# V2c.net
KiCad netlist of a schematic drawn in EAGLE
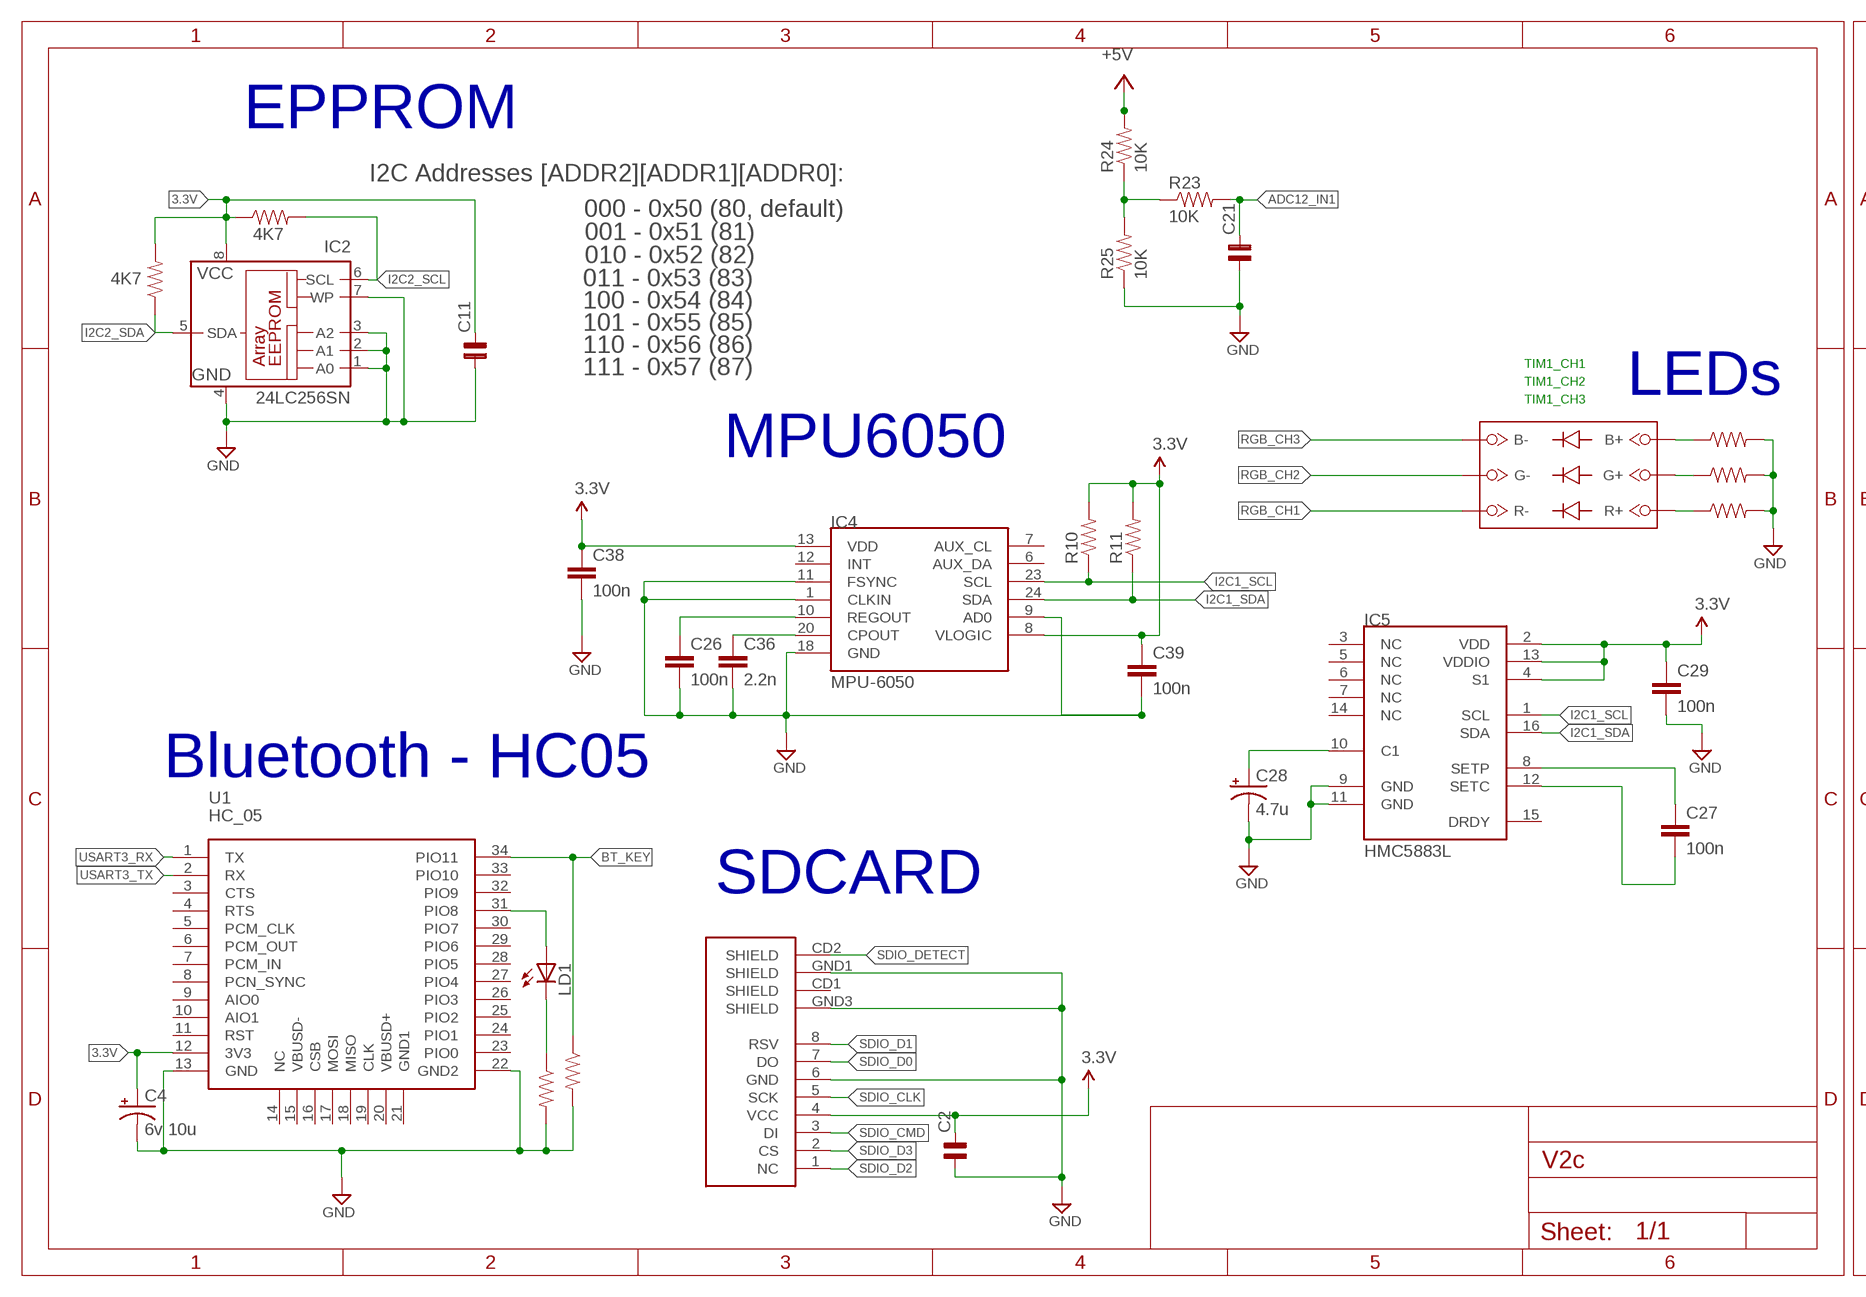
[diagram p0: schematic, sheet 1, part 1 of 2]
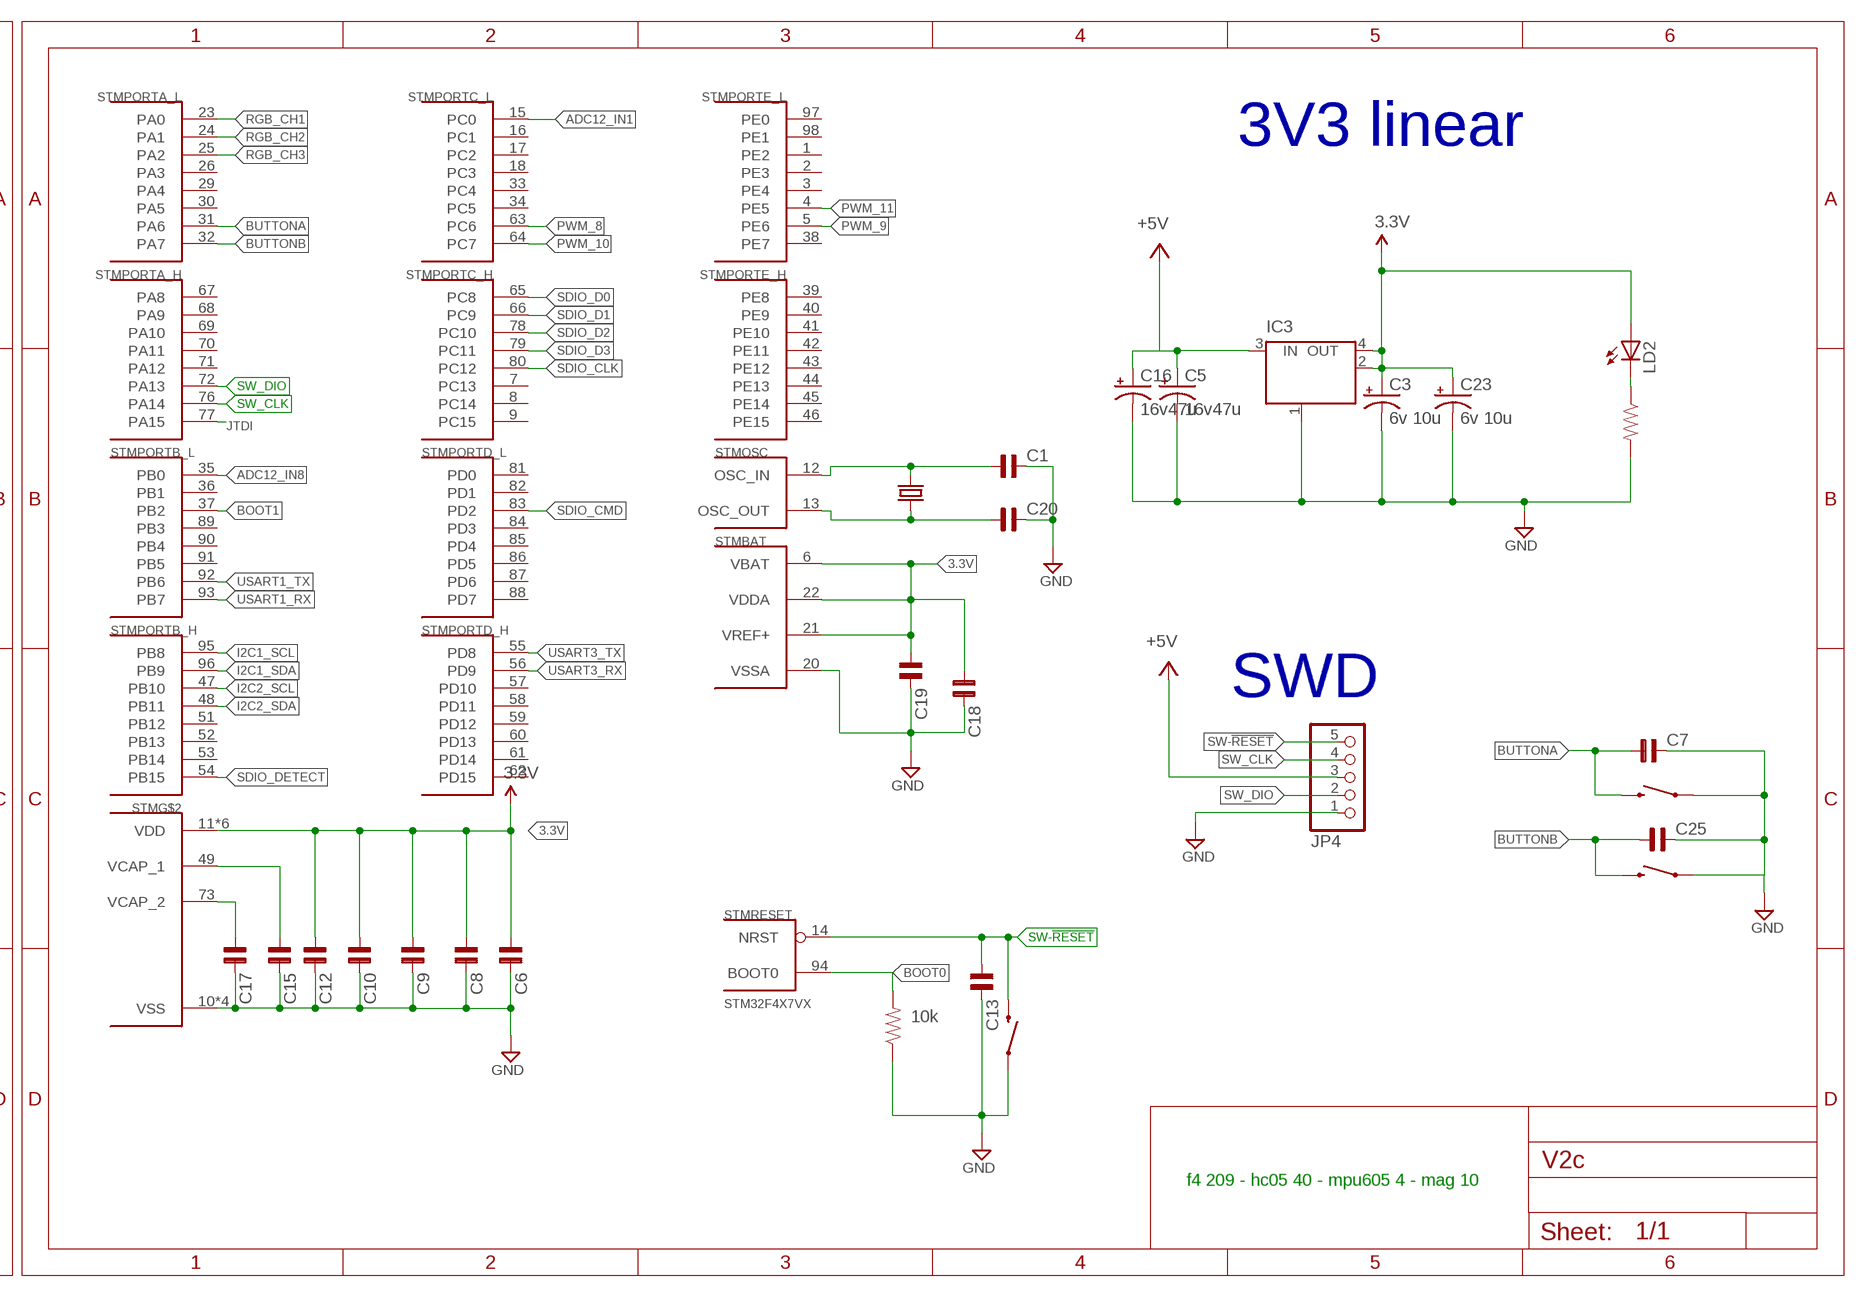
[diagram p1: schematic, sheet 1, part 2 of 2]

(export (version "E")
  (design (tool "Eeschema 10.0.6"))
  (components
    (comp (ref "C1")
      (value "C-NP-SMD-0603")
      (footprint "eagle-import:C-0603")
      (libsource (lib "eagle-import") (part "C-NP-SMD-0603"))
    )
    (comp (ref "C2")
      (value "C-NP-SMD-0603")
      (footprint "eagle-import:C-0603")
      (libsource (lib "eagle-import") (part "C-NP-SMD-0603"))
    )
    (comp (ref "C3")
      (value "6v 10u")
      (footprint "eagle-import:SMC_C")
      (libsource (lib "eagle-import") (part "CPOL-USSMCC"))
    )
    (comp (ref "C4")
      (value "6v 10u")
      (footprint "eagle-import:SMC_A")
      (libsource (lib "eagle-import") (part "CPOL-USSMCA"))
    )
    (comp (ref "C5")
      (value "16v47u")
      (footprint "eagle-import:SMC_C")
      (libsource (lib "eagle-import") (part "CPOL-USSMCC"))
    )
    (comp (ref "C6")
      (value "C-NP-SMD-0603")
      (footprint "eagle-import:C-0603")
      (libsource (lib "eagle-import") (part "C-NP-SMD-0603"))
    )
    (comp (ref "C7")
      (value "C-NP-SMD-0603")
      (footprint "eagle-import:C-0603")
      (libsource (lib "eagle-import") (part "C-NP-SMD-0603"))
    )
    (comp (ref "C8")
      (value "C-NP-SMD-0603")
      (footprint "eagle-import:C-0603")
      (libsource (lib "eagle-import") (part "C-NP-SMD-0603"))
    )
    (comp (ref "C9")
      (value "C-NP-SMD-0603")
      (footprint "eagle-import:C-0603")
      (libsource (lib "eagle-import") (part "C-NP-SMD-0603"))
    )
    (comp (ref "C10")
      (value "C-NP-SMD-0603")
      (footprint "eagle-import:C-0603")
      (libsource (lib "eagle-import") (part "C-NP-SMD-0603"))
    )
    (comp (ref "C11")
      (value "C-NP-SMD-0603")
      (footprint "eagle-import:C-0603")
      (libsource (lib "eagle-import") (part "C-NP-SMD-0603"))
    )
    (comp (ref "C12")
      (value "C-NP-SMD-0603")
      (footprint "eagle-import:C-0603")
      (libsource (lib "eagle-import") (part "C-NP-SMD-0603"))
    )
    (comp (ref "C13")
      (value "C-NP-SMD-0603")
      (footprint "eagle-import:C-0603")
      (libsource (lib "eagle-import") (part "C-NP-SMD-0603"))
    )
    (comp (ref "C15")
      (value "C-NP-SMD-0603")
      (footprint "eagle-import:C-0603")
      (libsource (lib "eagle-import") (part "C-NP-SMD-0603"))
    )
    (comp (ref "C16")
      (value "16v47u")
      (footprint "eagle-import:SMC_C")
      (libsource (lib "eagle-import") (part "CPOL-USSMCC"))
    )
    (comp (ref "C17")
      (value "C-NP-SMD-0603")
      (footprint "eagle-import:C-0603")
      (libsource (lib "eagle-import") (part "C-NP-SMD-0603"))
    )
    (comp (ref "C18")
      (value "C-NP-SMD-0603")
      (footprint "eagle-import:C-0603")
      (libsource (lib "eagle-import") (part "C-NP-SMD-0603"))
    )
    (comp (ref "C19")
      (value "C-NP-SMD-0603")
      (footprint "eagle-import:C-0603")
      (libsource (lib "eagle-import") (part "C-NP-SMD-0603"))
    )
    (comp (ref "C20")
      (value "C-NP-SMD-0603")
      (footprint "eagle-import:C-0603")
      (libsource (lib "eagle-import") (part "C-NP-SMD-0603"))
    )
    (comp (ref "C21")
      (value "C-NP-SMD-0603")
      (footprint "eagle-import:C-0603")
      (libsource (lib "eagle-import") (part "C-NP-SMD-0603"))
    )
    (comp (ref "C23")
      (value "6v 10u")
      (footprint "eagle-import:SMC_C")
      (libsource (lib "eagle-import") (part "CPOL-USSMCC"))
    )
    (comp (ref "C25")
      (value "C-NP-SMD-0603")
      (footprint "eagle-import:C-0603")
      (libsource (lib "eagle-import") (part "C-NP-SMD-0603"))
    )
    (comp (ref "C26")
      (value "100n")
      (footprint "eagle-import:SPARKFUN_0603-CAP")
      (libsource (lib "eagle-import") (part "SPARKFUN_CAP0603-CAP"))
    )
    (comp (ref "C27")
      (value "100n")
      (footprint "eagle-import:SPARKFUN_0603-CAP")
      (libsource (lib "eagle-import") (part "SPARKFUN_CAP0603-CAP"))
    )
    (comp (ref "C28")
      (value "4.7u")
      (footprint "eagle-import:SMC_A")
      (libsource (lib "eagle-import") (part "CPOL-USSMCA"))
    )
    (comp (ref "C29")
      (value "100n")
      (footprint "eagle-import:SPARKFUN_0603-CAP")
      (libsource (lib "eagle-import") (part "SPARKFUN_CAP0603-CAP"))
    )
    (comp (ref "C36")
      (value "2.2n")
      (footprint "eagle-import:SPARKFUN_0603-CAP")
      (libsource (lib "eagle-import") (part "SPARKFUN_CAP0603-CAP"))
    )
    (comp (ref "C38")
      (value "100n")
      (footprint "eagle-import:SPARKFUN_0603-CAP")
      (libsource (lib "eagle-import") (part "SPARKFUN_CAP0603-CAP"))
    )
    (comp (ref "C39")
      (value "100n")
      (footprint "eagle-import:SPARKFUN_0603-CAP")
      (libsource (lib "eagle-import") (part "SPARKFUN_CAP0603-CAP"))
    )
    (comp (ref "IC2")
      (value "24LC256SN")
      (footprint "eagle-import:SO-08")
      (fields (field (name "MF") "MICROCHIP") (field (name "MPN") "24LC256-I/SN"))
      (libsource (lib "eagle-import") (part "24SNLC256"))
    )
    (comp (ref "IC3")
      (value "LINEAR_MC33269ST-3.3T3")
      (footprint "eagle-import:LINEAR_SOT223")
      (libsource (lib "eagle-import") (part "LINEAR_MC33269ST-3.3T3"))
    )
    (comp (ref "IC4")
      (value "MPU-6050")
      (footprint "eagle-import:TESTING_QFN-24-4MM2")
      (libsource (lib "eagle-import") (part "TESTING_MPU-6050-1"))
    )
    (comp (ref "IC5")
      (value "HMC5883L")
      (footprint "eagle-import:SPARKFUN_16LPCC")
      (libsource (lib "eagle-import") (part "SPARKFUN_HMC5883LSMD"))
    )
    (comp (ref "JP4")
      (value "PINHD-1X5_2.54-90°")
      (footprint "eagle-import:1X05_90")
      (libsource (lib "eagle-import") (part "PINHD-1X5_2.54-90°"))
    )
    (comp (ref "LD1")
      (value "LEDCHIPLED_0603")
      (footprint "eagle-import:CHIPLED_0603")
      (libsource (lib "eagle-import") (part "LEDCHIPLED_0603"))
    )
    (comp (ref "LD2")
      (value "LEDCHIPLED_0603")
      (footprint "eagle-import:CHIPLED_0603")
      (libsource (lib "eagle-import") (part "LEDCHIPLED_0603"))
    )
    (comp (ref "R1")
      (value "10K")
      (footprint "eagle-import:SPARKFUN_0603-RES")
      (libsource (lib "eagle-import") (part "Robotech_RCL_SPARKFUN_RESISTOR0603-RES"))
    )
    (comp (ref "R2")
      (value "10K")
      (footprint "eagle-import:SPARKFUN_0603-RES")
      (libsource (lib "eagle-import") (part "Robotech_RCL_SPARKFUN_RESISTOR0603-RES"))
    )
    (comp (ref "R3")
      (value "10K")
      (footprint "eagle-import:SPARKFUN_0603-RES")
      (libsource (lib "eagle-import") (part "Robotech_RCL_SPARKFUN_RESISTOR0603-RES"))
    )
    (comp (ref "R5")
      (value "10K")
      (footprint "eagle-import:SPARKFUN_0603-RES")
      (libsource (lib "eagle-import") (part "Robotech_RCL_SPARKFUN_RESISTOR0603-RES"))
    )
    (comp (ref "R6")
      (value "10K")
      (footprint "eagle-import:SPARKFUN_0603-RES")
      (libsource (lib "eagle-import") (part "Robotech_RCL_SPARKFUN_RESISTOR0603-RES"))
    )
    (comp (ref "R7")
      (value "10k")
      (footprint "eagle-import:SPARKFUN_0603-RES")
      (libsource (lib "eagle-import") (part "Robotech_RCL_SPARKFUN_RESISTOR0603-RES"))
    )
    (comp (ref "R9")
      (value "10K")
      (footprint "eagle-import:SPARKFUN_0603-RES")
      (libsource (lib "eagle-import") (part "Robotech_RCL_SPARKFUN_RESISTOR0603-RES"))
    )
    (comp (ref "R10")
      (value "SPARKFUN_RESISTOR0603-RES")
      (footprint "eagle-import:SPARKFUN_0603-RES")
      (libsource (lib "eagle-import") (part "SPARKFUN_RESISTOR0603-RES"))
    )
    (comp (ref "R11")
      (value "SPARKFUN_RESISTOR0603-RES")
      (footprint "eagle-import:SPARKFUN_0603-RES")
      (libsource (lib "eagle-import") (part "SPARKFUN_RESISTOR0603-RES"))
    )
    (comp (ref "R15")
      (value "4K7")
      (footprint "eagle-import:SPARKFUN_0603-RES")
      (libsource (lib "eagle-import") (part "Robotech_RCL_SPARKFUN_RESISTOR0603-RES"))
    )
    (comp (ref "R16")
      (value "4K7")
      (footprint "eagle-import:SPARKFUN_0603-RES")
      (libsource (lib "eagle-import") (part "Robotech_RCL_SPARKFUN_RESISTOR0603-RES"))
    )
    (comp (ref "R23")
      (value "10K")
      (footprint "eagle-import:SPARKFUN_0603-RES")
      (libsource (lib "eagle-import") (part "Robotech_RCL_SPARKFUN_RESISTOR0603-RES"))
    )
    (comp (ref "R24")
      (value "10K")
      (footprint "eagle-import:SPARKFUN_0603-RES")
      (libsource (lib "eagle-import") (part "Robotech_RCL_SPARKFUN_RESISTOR0603-RES"))
    )
    (comp (ref "R25")
      (value "10K")
      (footprint "eagle-import:SPARKFUN_0603-RES")
      (libsource (lib "eagle-import") (part "Robotech_RCL_SPARKFUN_RESISTOR0603-RES"))
    )
    (comp (ref "S1")
      (value "RESET")
      (footprint "eagle-import:TACTILE-SWITCH-1101NE")
      (fields (field (name "PARTNO") "EVQ-P7J01P"))
      (libsource (lib "eagle-import") (part "SWITCH-MOMENTARY-2-SMD-1101NE"))
    )
    (comp (ref "S2")
      (value "RESET")
      (footprint "eagle-import:TACTILE-SWITCH-1101NE")
      (fields (field (name "PARTNO") "EVQ-P7J01P"))
      (libsource (lib "eagle-import") (part "SWITCH-MOMENTARY-2-SMD-1101NE"))
    )
    (comp (ref "S4")
      (value "RESET")
      (footprint "eagle-import:TACTILE-SWITCH-1101NE")
      (fields (field (name "PARTNO") "EVQ-P7J01P"))
      (libsource (lib "eagle-import") (part "SWITCH-MOMENTARY-2-SMD-1101NE"))
    )
    (comp (ref "SDCARD2")
      (value "microSD Socket")
      (footprint "eagle-import:MICRO-SD-SOCKET-PP")
      (libsource (lib "eagle-import") (part "USD-SOCKETNEW"))
    )
    (comp (ref "STM")
      (value "STM32F4X7VX")
      (footprint "eagle-import:TQFP100")
      (fields (field (name "PARTNO") "STM32F427VI"))
      (libsource (lib "eagle-import") (part "STM32F4X7VX"))
    )
    (comp (ref "U$12")
      (value "RGB_LED")
      (footprint "eagle-import:SMD")
      (libsource (lib "eagle-import") (part "RGB_LED"))
    )
    (comp (ref "U1")
      (value "HC_05")
      (footprint "eagle-import:BLUETOOTH_SMD")
      (libsource (lib "eagle-import") (part "HC_05"))
    )
    (comp (ref "Y1")
      (value "CRYSTALHC49US")
      (footprint "eagle-import:HC49US")
      (libsource (lib "eagle-import") (part "CRYSTALHC49US"))
    )
  )
  (nets
    (net (code "1") (name "+5V") (class "Default")
      (node (ref "C16") (pin "+") (pinfunction "+_+") (pintype "passive"))
      (node (ref "C5") (pin "+") (pinfunction "+_+") (pintype "passive"))
      (node (ref "IC3") (pin "3") (pinfunction "IN_3") (pintype "input"))
      (node (ref "JP4") (pin "3") (pinfunction "3_3") (pintype "passive"))
      (node (ref "R24") (pin "2") (pinfunction "2_2") (pintype "passive"))
    )
    (net (code "2") (name "/JTDI") (class "Default")
      (node (ref "STM") (pin "77") (pinfunction "PA15_77") (pintype "bidirectional"))
    )
    (net (code "3") (name "/SW-~{RESET}") (class "Default")
      (node (ref "C13") (pin "1") (pinfunction "1_1") (pintype "passive"))
      (node (ref "JP4") (pin "5") (pinfunction "5_5") (pintype "passive"))
      (node (ref "S1") (pin "P$2") (pinfunction "2_P$2") (pintype "passive"))
      (node (ref "STM") (pin "14") (pinfunction "NRST_14") (pintype "input"))
    )
    (net (code "4") (name "3.3V") (class "Default")
      (node (ref "C10") (pin "1") (pinfunction "1_1") (pintype "passive"))
      (node (ref "C11") (pin "2") (pinfunction "2_2") (pintype "passive"))
      (node (ref "C12") (pin "1") (pinfunction "1_1") (pintype "passive"))
      (node (ref "C18") (pin "1") (pinfunction "1_1") (pintype "passive"))
      (node (ref "C19") (pin "1") (pinfunction "1_1") (pintype "passive"))
      (node (ref "C2") (pin "2") (pinfunction "2_2") (pintype "passive"))
      (node (ref "C23") (pin "+") (pinfunction "+_+") (pintype "passive"))
      (node (ref "C29") (pin "1") (pinfunction "1_1") (pintype "passive"))
      (node (ref "C3") (pin "+") (pinfunction "+_+") (pintype "passive"))
      (node (ref "C38") (pin "1") (pinfunction "1_1") (pintype "passive"))
      (node (ref "C39") (pin "1") (pinfunction "1_1") (pintype "passive"))
      (node (ref "C4") (pin "+") (pinfunction "+_+") (pintype "passive"))
      (node (ref "C6") (pin "1") (pinfunction "1_1") (pintype "passive"))
      (node (ref "C8") (pin "1") (pinfunction "1_1") (pintype "passive"))
      (node (ref "C9") (pin "1") (pinfunction "1_1") (pintype "passive"))
      (node (ref "IC2") (pin "8") (pinfunction "VCC_8") (pintype "power_in"))
      (node (ref "IC3") (pin "2") (pinfunction "OUT_2") (pintype "passive"))
      (node (ref "IC3") (pin "4") (pinfunction "OUT_4") (pintype "passive"))
      (node (ref "IC4") (pin "13") (pinfunction "VDD_13") (pintype "bidirectional"))
      (node (ref "IC4") (pin "8") (pinfunction "VLOGIC_8") (pintype "bidirectional"))
      (node (ref "IC5") (pin "13") (pinfunction "VDDIO_13") (pintype "bidirectional"))
      (node (ref "IC5") (pin "2") (pinfunction "VDD_2") (pintype "bidirectional"))
      (node (ref "IC5") (pin "4") (pinfunction "S1_4") (pintype "bidirectional"))
      (node (ref "LD2") (pin "A") (pinfunction "A_A") (pintype "passive"))
      (node (ref "R10") (pin "2") (pinfunction "2_2") (pintype "passive"))
      (node (ref "R11") (pin "2") (pinfunction "2_2") (pintype "passive"))
      (node (ref "R15") (pin "1") (pinfunction "1_1") (pintype "passive"))
      (node (ref "R16") (pin "2") (pinfunction "2_2") (pintype "passive"))
      (node (ref "SDCARD2") (pin "4") (pinfunction "VCC_4") (pintype "bidirectional"))
      (node (ref "STM") (pin "100") (pinfunction "VDD_100") (pintype "power_in"))
      (node (ref "STM") (pin "11") (pinfunction "VDD_11") (pintype "power_in"))
      (node (ref "STM") (pin "19") (pinfunction "VDD_19") (pintype "power_in"))
      (node (ref "STM") (pin "21") (pinfunction "VREF+_21") (pintype "input"))
      (node (ref "STM") (pin "22") (pinfunction "VDDA_22") (pintype "power_in"))
      (node (ref "STM") (pin "28") (pinfunction "VDD_28") (pintype "power_in"))
      (node (ref "STM") (pin "50") (pinfunction "VDD_50") (pintype "power_in"))
      (node (ref "STM") (pin "6") (pinfunction "VBAT_6") (pintype "power_in"))
      (node (ref "STM") (pin "75") (pinfunction "VDD_75") (pintype "power_in"))
      (node (ref "U1") (pin "12") (pinfunction "3V3_12") (pintype "bidirectional"))
    )
    (net (code "5") (name "ADC12_IN1") (class "Default")
      (node (ref "C21") (pin "2") (pinfunction "2_2") (pintype "passive"))
      (node (ref "R23") (pin "2") (pinfunction "2_2") (pintype "passive"))
      (node (ref "STM") (pin "15") (pinfunction "PC0_15") (pintype "bidirectional"))
    )
    (net (code "6") (name "ADC12_IN8") (class "Default")
      (node (ref "STM") (pin "35") (pinfunction "PB0_35") (pintype "bidirectional"))
    )
    (net (code "7") (name "BOOT0") (class "Default")
      (node (ref "R7") (pin "2") (pinfunction "2_2") (pintype "passive"))
      (node (ref "STM") (pin "94") (pinfunction "BOOT0_94") (pintype "input"))
    )
    (net (code "8") (name "BOOT1") (class "Default")
      (node (ref "STM") (pin "37") (pinfunction "PB2_37") (pintype "bidirectional"))
    )
    (net (code "9") (name "BT_KEY") (class "Default")
      (node (ref "R5") (pin "1") (pinfunction "1_1") (pintype "passive"))
      (node (ref "U1") (pin "34") (pinfunction "PIO11_34") (pintype "bidirectional"))
    )
    (net (code "10") (name "BUTTONA") (class "Default")
      (node (ref "C7") (pin "1") (pinfunction "1_1") (pintype "passive"))
      (node (ref "S4") (pin "P$2") (pinfunction "2_P$2") (pintype "passive"))
      (node (ref "STM") (pin "31") (pinfunction "PA6_31") (pintype "bidirectional"))
    )
    (net (code "11") (name "BUTTONB") (class "Default")
      (node (ref "C25") (pin "1") (pinfunction "1_1") (pintype "passive"))
      (node (ref "S2") (pin "P$2") (pinfunction "2_P$2") (pintype "passive"))
      (node (ref "STM") (pin "32") (pinfunction "PA7_32") (pintype "bidirectional"))
    )
    (net (code "12") (name "GND") (class "Default")
      (node (ref "C1") (pin "2") (pinfunction "2_2") (pintype "passive"))
      (node (ref "C10") (pin "2") (pinfunction "2_2") (pintype "passive"))
      (node (ref "C11") (pin "1") (pinfunction "1_1") (pintype "passive"))
      (node (ref "C12") (pin "2") (pinfunction "2_2") (pintype "passive"))
      (node (ref "C13") (pin "2") (pinfunction "2_2") (pintype "passive"))
      (node (ref "C15") (pin "2") (pinfunction "2_2") (pintype "passive"))
      (node (ref "C16") (pin "-") (pinfunction "-_-") (pintype "passive"))
      (node (ref "C17") (pin "2") (pinfunction "2_2") (pintype "passive"))
      (node (ref "C18") (pin "2") (pinfunction "2_2") (pintype "passive"))
      (node (ref "C19") (pin "2") (pinfunction "2_2") (pintype "passive"))
      (node (ref "C2") (pin "1") (pinfunction "1_1") (pintype "passive"))
      (node (ref "C20") (pin "2") (pinfunction "2_2") (pintype "passive"))
      (node (ref "C21") (pin "1") (pinfunction "1_1") (pintype "passive"))
      (node (ref "C23") (pin "-") (pinfunction "-_-") (pintype "passive"))
      (node (ref "C25") (pin "2") (pinfunction "2_2") (pintype "passive"))
      (node (ref "C26") (pin "2") (pinfunction "2_2") (pintype "passive"))
      (node (ref "C28") (pin "-") (pinfunction "-_-") (pintype "passive"))
      (node (ref "C29") (pin "2") (pinfunction "2_2") (pintype "passive"))
      (node (ref "C3") (pin "-") (pinfunction "-_-") (pintype "passive"))
      (node (ref "C36") (pin "2") (pinfunction "2_2") (pintype "passive"))
      (node (ref "C38") (pin "2") (pinfunction "2_2") (pintype "passive"))
      (node (ref "C39") (pin "2") (pinfunction "2_2") (pintype "passive"))
      (node (ref "C4") (pin "-") (pinfunction "-_-") (pintype "passive"))
      (node (ref "C5") (pin "-") (pinfunction "-_-") (pintype "passive"))
      (node (ref "C6") (pin "2") (pinfunction "2_2") (pintype "passive"))
      (node (ref "C7") (pin "2") (pinfunction "2_2") (pintype "passive"))
      (node (ref "C8") (pin "2") (pinfunction "2_2") (pintype "passive"))
      (node (ref "C9") (pin "2") (pinfunction "2_2") (pintype "passive"))
      (node (ref "IC2") (pin "1") (pinfunction "A0_1") (pintype "input"))
      (node (ref "IC2") (pin "2") (pinfunction "A1_2") (pintype "input"))
      (node (ref "IC2") (pin "3") (pinfunction "A2_3") (pintype "input"))
      (node (ref "IC2") (pin "4") (pinfunction "GND_4") (pintype "power_in"))
      (node (ref "IC2") (pin "7") (pinfunction "WP_7") (pintype "input"))
      (node (ref "IC3") (pin "1") (pinfunction "GND/ADJ_1") (pintype "input"))
      (node (ref "IC4") (pin "1") (pinfunction "CLKIN_1") (pintype "bidirectional"))
      (node (ref "IC4") (pin "11") (pinfunction "FSYNC_11") (pintype "bidirectional"))
      (node (ref "IC4") (pin "18") (pinfunction "GND_18") (pintype "bidirectional"))
      (node (ref "IC4") (pin "9") (pinfunction "AD0_9") (pintype "bidirectional"))
      (node (ref "IC5") (pin "11") (pinfunction "GND_11") (pintype "bidirectional"))
      (node (ref "IC5") (pin "9") (pinfunction "GND_9") (pintype "bidirectional"))
      (node (ref "JP4") (pin "1") (pinfunction "1_1") (pintype "passive"))
      (node (ref "R1") (pin "2") (pinfunction "2_2") (pintype "passive"))
      (node (ref "R2") (pin "2") (pinfunction "2_2") (pintype "passive"))
      (node (ref "R25") (pin "1") (pinfunction "1_1") (pintype "passive"))
      (node (ref "R3") (pin "2") (pinfunction "2_2") (pintype "passive"))
      (node (ref "R5") (pin "2") (pinfunction "2_2") (pintype "passive"))
      (node (ref "R6") (pin "2") (pinfunction "2_2") (pintype "passive"))
      (node (ref "R7") (pin "1") (pinfunction "1_1") (pintype "passive"))
      (node (ref "R9") (pin "2") (pinfunction "2_2") (pintype "passive"))
      (node (ref "S1") (pin "P$1") (pinfunction "1_P$1") (pintype "passive"))
      (node (ref "S2") (pin "P$1") (pinfunction "1_P$1") (pintype "passive"))
      (node (ref "S4") (pin "P$1") (pinfunction "1_P$1") (pintype "passive"))
      (node (ref "SDCARD2") (pin "6") (pinfunction "GND_6") (pintype "bidirectional"))
      (node (ref "SDCARD2") (pin "GND1") (pinfunction "SHIELD_GND1") (pintype "bidirectional"))
      (node (ref "SDCARD2") (pin "GND3") (pinfunction "SHIELD_GND3") (pintype "bidirectional"))
      (node (ref "STM") (pin "10") (pinfunction "VSS_10") (pintype "power_in"))
      (node (ref "STM") (pin "20") (pinfunction "VSSA_20") (pintype "power_in"))
      (node (ref "STM") (pin "27") (pinfunction "VSS_27") (pintype "power_in"))
      (node (ref "STM") (pin "74") (pinfunction "VSS_74") (pintype "power_in"))
      (node (ref "STM") (pin "99") (pinfunction "VSS_99") (pintype "power_in"))
      (node (ref "U1") (pin "13") (pinfunction "GND_13") (pintype "bidirectional"))
      (node (ref "U1") (pin "22") (pinfunction "GND2_22") (pintype "bidirectional"))
    )
    (net (code "13") (name "I2C1_SCL") (class "Default")
      (node (ref "IC4") (pin "23") (pinfunction "SCL_23") (pintype "bidirectional"))
      (node (ref "IC5") (pin "1") (pinfunction "SCL_1") (pintype "bidirectional"))
      (node (ref "R10") (pin "1") (pinfunction "1_1") (pintype "passive"))
      (node (ref "STM") (pin "95") (pinfunction "PB8_95") (pintype "bidirectional"))
    )
    (net (code "14") (name "I2C1_SDA") (class "Default")
      (node (ref "IC4") (pin "24") (pinfunction "SDA_24") (pintype "bidirectional"))
      (node (ref "IC5") (pin "16") (pinfunction "SDA_16") (pintype "bidirectional"))
      (node (ref "R11") (pin "1") (pinfunction "1_1") (pintype "passive"))
      (node (ref "STM") (pin "96") (pinfunction "PB9_96") (pintype "bidirectional"))
    )
    (net (code "15") (name "I2C2_SCL") (class "Default")
      (node (ref "IC2") (pin "6") (pinfunction "SCL_6") (pintype "input"))
      (node (ref "R15") (pin "2") (pinfunction "2_2") (pintype "passive"))
      (node (ref "STM") (pin "47") (pinfunction "PB10_47") (pintype "bidirectional"))
    )
    (net (code "16") (name "I2C2_SDA") (class "Default")
      (node (ref "IC2") (pin "5") (pinfunction "SDA_5") (pintype "bidirectional"))
      (node (ref "R16") (pin "1") (pinfunction "1_1") (pintype "passive"))
      (node (ref "STM") (pin "48") (pinfunction "PB11_48") (pintype "bidirectional"))
    )
    (net (code "17") (name "Net-(IC4-CPOUT)") (class "Default")
      (node (ref "C36") (pin "1") (pinfunction "1_1") (pintype "passive"))
      (node (ref "IC4") (pin "20") (pinfunction "CPOUT_20") (pintype "bidirectional"))
    )
    (net (code "18") (name "Net-(IC4-REGOUT)") (class "Default")
      (node (ref "C26") (pin "1") (pinfunction "1_1") (pintype "passive"))
      (node (ref "IC4") (pin "10") (pinfunction "REGOUT_10") (pintype "bidirectional"))
    )
    (net (code "19") (name "Net-(IC5-C1)") (class "Default")
      (node (ref "C28") (pin "+") (pinfunction "+_+") (pintype "passive"))
      (node (ref "IC5") (pin "10") (pinfunction "C1_10") (pintype "bidirectional"))
    )
    (net (code "20") (name "Net-(IC5-SETC)") (class "Default")
      (node (ref "C27") (pin "2") (pinfunction "2_2") (pintype "passive"))
      (node (ref "IC5") (pin "12") (pinfunction "SETC_12") (pintype "bidirectional"))
    )
    (net (code "21") (name "Net-(IC5-SETP)") (class "Default")
      (node (ref "C27") (pin "1") (pinfunction "1_1") (pintype "passive"))
      (node (ref "IC5") (pin "8") (pinfunction "SETP_8") (pintype "bidirectional"))
    )
    (net (code "22") (name "Net-(LD1-PadC)") (class "Default")
      (node (ref "LD1") (pin "C") (pinfunction "C_C") (pintype "passive"))
      (node (ref "R9") (pin "1") (pinfunction "1_1") (pintype "passive"))
    )
    (net (code "23") (name "Net-(LD2-PadC)") (class "Default")
      (node (ref "LD2") (pin "C") (pinfunction "C_C") (pintype "passive"))
      (node (ref "R1") (pin "1") (pinfunction "1_1") (pintype "passive"))
    )
    (net (code "24") (name "Net-(R2-Pad1)") (class "Default")
      (node (ref "R2") (pin "1") (pinfunction "1_1") (pintype "passive"))
      (node (ref "U$12") (pin "B+") (pinfunction "B+_B+") (pintype "bidirectional"))
    )
    (net (code "25") (name "Net-(R3-Pad1)") (class "Default")
      (node (ref "R3") (pin "1") (pinfunction "1_1") (pintype "passive"))
      (node (ref "U$12") (pin "G+") (pinfunction "G+_G+") (pintype "bidirectional"))
    )
    (net (code "26") (name "Net-(R6-Pad1)") (class "Default")
      (node (ref "R6") (pin "1") (pinfunction "1_1") (pintype "passive"))
      (node (ref "U$12") (pin "R+") (pinfunction "R+_R+") (pintype "bidirectional"))
    )
    (net (code "27") (name "Net-(R23-Pad1)") (class "Default")
      (node (ref "R23") (pin "1") (pinfunction "1_1") (pintype "passive"))
      (node (ref "R24") (pin "1") (pinfunction "1_1") (pintype "passive"))
      (node (ref "R25") (pin "2") (pinfunction "2_2") (pintype "passive"))
    )
    (net (code "28") (name "Net-(STMB-VCAP_1)") (class "Default")
      (node (ref "C15") (pin "1") (pinfunction "1_1") (pintype "passive"))
      (node (ref "STM") (pin "49") (pinfunction "VCAP_1_49") (pintype "power_in"))
    )
    (net (code "29") (name "Net-(STMB-VCAP_2)") (class "Default")
      (node (ref "C17") (pin "1") (pinfunction "1_1") (pintype "passive"))
      (node (ref "STM") (pin "73") (pinfunction "VCAP_2_73") (pintype "power_in"))
    )
    (net (code "30") (name "Net-(STMC-OSC_IN)") (class "Default")
      (node (ref "C1") (pin "1") (pinfunction "1_1") (pintype "passive"))
      (node (ref "STM") (pin "12") (pinfunction "OSC_IN_12") (pintype "input"))
      (node (ref "Y1") (pin "2") (pinfunction "2_2") (pintype "passive"))
    )
    (net (code "31") (name "Net-(STMC-OSC_OUT)") (class "Default")
      (node (ref "C20") (pin "1") (pinfunction "1_1") (pintype "passive"))
      (node (ref "STM") (pin "13") (pinfunction "OSC_OUT_13") (pintype "output"))
      (node (ref "Y1") (pin "1") (pinfunction "1_1") (pintype "passive"))
    )
    (net (code "32") (name "Net-(U1-PIO8)") (class "Default")
      (node (ref "LD1") (pin "A") (pinfunction "A_A") (pintype "passive"))
      (node (ref "U1") (pin "31") (pinfunction "PIO8_31") (pintype "bidirectional"))
    )
    (net (code "33") (name "PWM_8") (class "Default")
      (node (ref "STM") (pin "63") (pinfunction "PC6_63") (pintype "bidirectional"))
    )
    (net (code "34") (name "PWM_9") (class "Default")
      (node (ref "STM") (pin "5") (pinfunction "PE6_5") (pintype "bidirectional"))
    )
    (net (code "35") (name "PWM_10") (class "Default")
      (node (ref "STM") (pin "64") (pinfunction "PC7_64") (pintype "bidirectional"))
    )
    (net (code "36") (name "PWM_11") (class "Default")
      (node (ref "STM") (pin "4") (pinfunction "PE5_4") (pintype "bidirectional"))
    )
    (net (code "37") (name "RGB_CH1") (class "Default")
      (node (ref "STM") (pin "23") (pinfunction "PA0_23") (pintype "bidirectional"))
      (node (ref "U$12") (pin "R-") (pinfunction "R-_R-") (pintype "bidirectional"))
    )
    (net (code "38") (name "RGB_CH2") (class "Default")
      (node (ref "STM") (pin "24") (pinfunction "PA1_24") (pintype "bidirectional"))
      (node (ref "U$12") (pin "G-") (pinfunction "G-_G-") (pintype "bidirectional"))
    )
    (net (code "39") (name "RGB_CH3") (class "Default")
      (node (ref "STM") (pin "25") (pinfunction "PA2_25") (pintype "bidirectional"))
      (node (ref "U$12") (pin "B-") (pinfunction "B-_B-") (pintype "bidirectional"))
    )
    (net (code "40") (name "SDIO_CLK") (class "Default")
      (node (ref "SDCARD2") (pin "5") (pinfunction "SCK_5") (pintype "bidirectional"))
      (node (ref "STM") (pin "80") (pinfunction "PC12_80") (pintype "bidirectional"))
    )
    (net (code "41") (name "SDIO_CMD") (class "Default")
      (node (ref "SDCARD2") (pin "3") (pinfunction "DI_3") (pintype "bidirectional"))
      (node (ref "STM") (pin "83") (pinfunction "PD2_83") (pintype "bidirectional"))
    )
    (net (code "42") (name "SDIO_D0") (class "Default")
      (node (ref "SDCARD2") (pin "7") (pinfunction "DO_7") (pintype "bidirectional"))
      (node (ref "STM") (pin "65") (pinfunction "PC8_65") (pintype "bidirectional"))
    )
    (net (code "43") (name "SDIO_D1") (class "Default")
      (node (ref "SDCARD2") (pin "8") (pinfunction "RSV_8") (pintype "bidirectional"))
      (node (ref "STM") (pin "66") (pinfunction "PC9_66") (pintype "bidirectional"))
    )
    (net (code "44") (name "SDIO_D2") (class "Default")
      (node (ref "SDCARD2") (pin "1") (pinfunction "NC_1") (pintype "bidirectional"))
      (node (ref "STM") (pin "78") (pinfunction "PC10_78") (pintype "bidirectional"))
    )
    (net (code "45") (name "SDIO_D3") (class "Default")
      (node (ref "SDCARD2") (pin "2") (pinfunction "CS_2") (pintype "bidirectional"))
      (node (ref "STM") (pin "79") (pinfunction "PC11_79") (pintype "bidirectional"))
    )
    (net (code "46") (name "SDIO_DETECT") (class "Default")
      (node (ref "SDCARD2") (pin "CD2") (pinfunction "SHIELD_CD2") (pintype "bidirectional"))
      (node (ref "STM") (pin "54") (pinfunction "PB15_54") (pintype "bidirectional"))
    )
    (net (code "47") (name "SW_CLK") (class "Default")
      (node (ref "JP4") (pin "4") (pinfunction "4_4") (pintype "passive"))
      (node (ref "STM") (pin "76") (pinfunction "PA14_76") (pintype "bidirectional"))
    )
    (net (code "48") (name "SW_DIO") (class "Default")
      (node (ref "JP4") (pin "2") (pinfunction "2_2") (pintype "passive"))
      (node (ref "STM") (pin "72") (pinfunction "PA13_72") (pintype "bidirectional"))
    )
    (net (code "49") (name "USART1_RX") (class "Default")
      (node (ref "STM") (pin "93") (pinfunction "PB7_93") (pintype "bidirectional"))
    )
    (net (code "50") (name "USART1_TX") (class "Default")
      (node (ref "STM") (pin "92") (pinfunction "PB6_92") (pintype "bidirectional"))
    )
    (net (code "51") (name "USART3_RX") (class "Default")
      (node (ref "STM") (pin "56") (pinfunction "PD9_56") (pintype "bidirectional"))
      (node (ref "U1") (pin "1") (pinfunction "TX_1") (pintype "bidirectional"))
    )
    (net (code "52") (name "USART3_TX") (class "Default")
      (node (ref "STM") (pin "55") (pinfunction "PD8_55") (pintype "bidirectional"))
      (node (ref "U1") (pin "2") (pinfunction "RX_2") (pintype "bidirectional"))
    )
    (net (code "53") (name "unconnected-(IC4-AUX_CL-Pad7)") (class "Default")
      (node (ref "IC4") (pin "7") (pinfunction "AUX_CL_7") (pintype "bidirectional"))
    )
    (net (code "54") (name "unconnected-(IC4-AUX_DA-Pad6)") (class "Default")
      (node (ref "IC4") (pin "6") (pinfunction "AUX_DA_6") (pintype "bidirectional"))
    )
    (net (code "55") (name "unconnected-(IC4-INT-Pad12)") (class "Default")
      (node (ref "IC4") (pin "12") (pinfunction "INT_12") (pintype "bidirectional"))
    )
    (net (code "56") (name "unconnected-(IC5-DRDY-Pad15)") (class "Default")
      (node (ref "IC5") (pin "15") (pinfunction "DRDY_15") (pintype "bidirectional"))
    )
    (net (code "57") (name "unconnected-(IC5-NC-Pad3)") (class "Default")
      (node (ref "IC5") (pin "3") (pinfunction "NC_3") (pintype "bidirectional"))
    )
    (net (code "58") (name "unconnected-(IC5-NC-Pad5)") (class "Default")
      (node (ref "IC5") (pin "5") (pinfunction "NC_5") (pintype "bidirectional"))
    )
    (net (code "59") (name "unconnected-(IC5-NC-Pad6)") (class "Default")
      (node (ref "IC5") (pin "6") (pinfunction "NC_6") (pintype "bidirectional"))
    )
    (net (code "60") (name "unconnected-(IC5-NC-Pad7)") (class "Default")
      (node (ref "IC5") (pin "7") (pinfunction "NC_7") (pintype "bidirectional"))
    )
    (net (code "61") (name "unconnected-(IC5-NC-Pad14)") (class "Default")
      (node (ref "IC5") (pin "14") (pinfunction "NC_14") (pintype "bidirectional"))
    )
    (net (code "62") (name "unconnected-(SDCARD2-SHIELD-PadCD1)") (class "Default")
      (node (ref "SDCARD2") (pin "CD1") (pinfunction "SHIELD_CD1") (pintype "bidirectional"))
    )
    (net (code "63") (name "unconnected-(STMD-PA8-Pad67)") (class "Default")
      (node (ref "STM") (pin "67") (pinfunction "PA8_67") (pintype "bidirectional"))
    )
    (net (code "64") (name "unconnected-(STMD-PA9-Pad68)") (class "Default")
      (node (ref "STM") (pin "68") (pinfunction "PA9_68") (pintype "bidirectional"))
    )
    (net (code "65") (name "unconnected-(STMD-PA10-Pad69)") (class "Default")
      (node (ref "STM") (pin "69") (pinfunction "PA10_69") (pintype "bidirectional"))
    )
    (net (code "66") (name "unconnected-(STMD-PA11-Pad70)") (class "Default")
      (node (ref "STM") (pin "70") (pinfunction "PA11_70") (pintype "bidirectional"))
    )
    (net (code "67") (name "unconnected-(STMD-PA12-Pad71)") (class "Default")
      (node (ref "STM") (pin "71") (pinfunction "PA12_71") (pintype "bidirectional"))
    )
    (net (code "68") (name "unconnected-(STME-PA3-Pad26)") (class "Default")
      (node (ref "STM") (pin "26") (pinfunction "PA3_26") (pintype "bidirectional"))
    )
    (net (code "69") (name "unconnected-(STME-PA4-Pad29)") (class "Default")
      (node (ref "STM") (pin "29") (pinfunction "PA4_29") (pintype "bidirectional"))
    )
    (net (code "70") (name "unconnected-(STME-PA5-Pad30)") (class "Default")
      (node (ref "STM") (pin "30") (pinfunction "PA5_30") (pintype "bidirectional"))
    )
    (net (code "71") (name "unconnected-(STMF-PB12-Pad51)") (class "Default")
      (node (ref "STM") (pin "51") (pinfunction "PB12_51") (pintype "bidirectional"))
    )
    (net (code "72") (name "unconnected-(STMF-PB13-Pad52)") (class "Default")
      (node (ref "STM") (pin "52") (pinfunction "PB13_52") (pintype "bidirectional"))
    )
    (net (code "73") (name "unconnected-(STMF-PB14-Pad53)") (class "Default")
      (node (ref "STM") (pin "53") (pinfunction "PB14_53") (pintype "bidirectional"))
    )
    (net (code "74") (name "unconnected-(STMG-PB1-Pad36)") (class "Default")
      (node (ref "STM") (pin "36") (pinfunction "PB1_36") (pintype "bidirectional"))
    )
    (net (code "75") (name "unconnected-(STMG-PB3-Pad89)") (class "Default")
      (node (ref "STM") (pin "89") (pinfunction "PB3_89") (pintype "bidirectional"))
    )
    (net (code "76") (name "unconnected-(STMG-PB4-Pad90)") (class "Default")
      (node (ref "STM") (pin "90") (pinfunction "PB4_90") (pintype "bidirectional"))
    )
    (net (code "77") (name "unconnected-(STMG-PB5-Pad91)") (class "Default")
      (node (ref "STM") (pin "91") (pinfunction "PB5_91") (pintype "bidirectional"))
    )
    (net (code "78") (name "unconnected-(STMH-PC13-Pad7)") (class "Default")
      (node (ref "STM") (pin "7") (pinfunction "PC13_7") (pintype "bidirectional"))
    )
    (net (code "79") (name "unconnected-(STMH-PC14-Pad8)") (class "Default")
      (node (ref "STM") (pin "8") (pinfunction "PC14_8") (pintype "bidirectional"))
    )
    (net (code "80") (name "unconnected-(STMH-PC15-Pad9)") (class "Default")
      (node (ref "STM") (pin "9") (pinfunction "PC15_9") (pintype "bidirectional"))
    )
    (net (code "81") (name "unconnected-(STMI-PC1-Pad16)") (class "Default")
      (node (ref "STM") (pin "16") (pinfunction "PC1_16") (pintype "bidirectional"))
    )
    (net (code "82") (name "unconnected-(STMI-PC2-Pad17)") (class "Default")
      (node (ref "STM") (pin "17") (pinfunction "PC2_17") (pintype "bidirectional"))
    )
    (net (code "83") (name "unconnected-(STMI-PC3-Pad18)") (class "Default")
      (node (ref "STM") (pin "18") (pinfunction "PC3_18") (pintype "bidirectional"))
    )
    (net (code "84") (name "unconnected-(STMI-PC4-Pad33)") (class "Default")
      (node (ref "STM") (pin "33") (pinfunction "PC4_33") (pintype "bidirectional"))
    )
    (net (code "85") (name "unconnected-(STMI-PC5-Pad34)") (class "Default")
      (node (ref "STM") (pin "34") (pinfunction "PC5_34") (pintype "bidirectional"))
    )
    (net (code "86") (name "unconnected-(STMJ-PD10-Pad57)") (class "Default")
      (node (ref "STM") (pin "57") (pinfunction "PD10_57") (pintype "bidirectional"))
    )
    (net (code "87") (name "unconnected-(STMJ-PD11-Pad58)") (class "Default")
      (node (ref "STM") (pin "58") (pinfunction "PD11_58") (pintype "bidirectional"))
    )
    (net (code "88") (name "unconnected-(STMJ-PD12-Pad59)") (class "Default")
      (node (ref "STM") (pin "59") (pinfunction "PD12_59") (pintype "bidirectional"))
    )
    (net (code "89") (name "unconnected-(STMJ-PD13-Pad60)") (class "Default")
      (node (ref "STM") (pin "60") (pinfunction "PD13_60") (pintype "bidirectional"))
    )
    (net (code "90") (name "unconnected-(STMJ-PD14-Pad61)") (class "Default")
      (node (ref "STM") (pin "61") (pinfunction "PD14_61") (pintype "bidirectional"))
    )
    (net (code "91") (name "unconnected-(STMJ-PD15-Pad62)") (class "Default")
      (node (ref "STM") (pin "62") (pinfunction "PD15_62") (pintype "bidirectional"))
    )
    (net (code "92") (name "unconnected-(STMK-PD0-Pad81)") (class "Default")
      (node (ref "STM") (pin "81") (pinfunction "PD0_81") (pintype "bidirectional"))
    )
    (net (code "93") (name "unconnected-(STMK-PD1-Pad82)") (class "Default")
      (node (ref "STM") (pin "82") (pinfunction "PD1_82") (pintype "bidirectional"))
    )
    (net (code "94") (name "unconnected-(STMK-PD3-Pad84)") (class "Default")
      (node (ref "STM") (pin "84") (pinfunction "PD3_84") (pintype "bidirectional"))
    )
    (net (code "95") (name "unconnected-(STMK-PD4-Pad85)") (class "Default")
      (node (ref "STM") (pin "85") (pinfunction "PD4_85") (pintype "bidirectional"))
    )
    (net (code "96") (name "unconnected-(STMK-PD5-Pad86)") (class "Default")
      (node (ref "STM") (pin "86") (pinfunction "PD5_86") (pintype "bidirectional"))
    )
    (net (code "97") (name "unconnected-(STMK-PD6-Pad87)") (class "Default")
      (node (ref "STM") (pin "87") (pinfunction "PD6_87") (pintype "bidirectional"))
    )
    (net (code "98") (name "unconnected-(STMK-PD7-Pad88)") (class "Default")
      (node (ref "STM") (pin "88") (pinfunction "PD7_88") (pintype "bidirectional"))
    )
    (net (code "99") (name "unconnected-(STML-PE8-Pad39)") (class "Default")
      (node (ref "STM") (pin "39") (pinfunction "PE8_39") (pintype "bidirectional"))
    )
    (net (code "100") (name "unconnected-(STML-PE9-Pad40)") (class "Default")
      (node (ref "STM") (pin "40") (pinfunction "PE9_40") (pintype "bidirectional"))
    )
    (net (code "101") (name "unconnected-(STML-PE10-Pad41)") (class "Default")
      (node (ref "STM") (pin "41") (pinfunction "PE10_41") (pintype "bidirectional"))
    )
    (net (code "102") (name "unconnected-(STML-PE11-Pad42)") (class "Default")
      (node (ref "STM") (pin "42") (pinfunction "PE11_42") (pintype "bidirectional"))
    )
    (net (code "103") (name "unconnected-(STML-PE12-Pad43)") (class "Default")
      (node (ref "STM") (pin "43") (pinfunction "PE12_43") (pintype "bidirectional"))
    )
    (net (code "104") (name "unconnected-(STML-PE13-Pad44)") (class "Default")
      (node (ref "STM") (pin "44") (pinfunction "PE13_44") (pintype "bidirectional"))
    )
    (net (code "105") (name "unconnected-(STML-PE14-Pad45)") (class "Default")
      (node (ref "STM") (pin "45") (pinfunction "PE14_45") (pintype "bidirectional"))
    )
    (net (code "106") (name "unconnected-(STML-PE15-Pad46)") (class "Default")
      (node (ref "STM") (pin "46") (pinfunction "PE15_46") (pintype "bidirectional"))
    )
    (net (code "107") (name "unconnected-(STMM-PE0-Pad97)") (class "Default")
      (node (ref "STM") (pin "97") (pinfunction "PE0_97") (pintype "bidirectional"))
    )
    (net (code "108") (name "unconnected-(STMM-PE1-Pad98)") (class "Default")
      (node (ref "STM") (pin "98") (pinfunction "PE1_98") (pintype "bidirectional"))
    )
    (net (code "109") (name "unconnected-(STMM-PE2-Pad1)") (class "Default")
      (node (ref "STM") (pin "1") (pinfunction "PE2_1") (pintype "bidirectional"))
    )
    (net (code "110") (name "unconnected-(STMM-PE3-Pad2)") (class "Default")
      (node (ref "STM") (pin "2") (pinfunction "PE3_2") (pintype "bidirectional"))
    )
    (net (code "111") (name "unconnected-(STMM-PE4-Pad3)") (class "Default")
      (node (ref "STM") (pin "3") (pinfunction "PE4_3") (pintype "bidirectional"))
    )
    (net (code "112") (name "unconnected-(STMM-PE7-Pad38)") (class "Default")
      (node (ref "STM") (pin "38") (pinfunction "PE7_38") (pintype "bidirectional"))
    )
    (net (code "113") (name "unconnected-(U1-AIO0-Pad9)") (class "Default")
      (node (ref "U1") (pin "9") (pinfunction "AIO0_9") (pintype "bidirectional"))
    )
    (net (code "114") (name "unconnected-(U1-AIO1-Pad10)") (class "Default")
      (node (ref "U1") (pin "10") (pinfunction "AIO1_10") (pintype "bidirectional"))
    )
    (net (code "115") (name "unconnected-(U1-CLK-Pad19)") (class "Default")
      (node (ref "U1") (pin "19") (pinfunction "CLK_19") (pintype "bidirectional"))
    )
    (net (code "116") (name "unconnected-(U1-CSB-Pad16)") (class "Default")
      (node (ref "U1") (pin "16") (pinfunction "CSB_16") (pintype "bidirectional"))
    )
    (net (code "117") (name "unconnected-(U1-CTS-Pad3)") (class "Default")
      (node (ref "U1") (pin "3") (pinfunction "CTS_3") (pintype "bidirectional"))
    )
    (net (code "118") (name "unconnected-(U1-GND1-Pad21)") (class "Default")
      (node (ref "U1") (pin "21") (pinfunction "GND1_21") (pintype "bidirectional"))
    )
    (net (code "119") (name "unconnected-(U1-MISO-Pad18)") (class "Default")
      (node (ref "U1") (pin "18") (pinfunction "MISO_18") (pintype "bidirectional"))
    )
    (net (code "120") (name "unconnected-(U1-MOSI-Pad17)") (class "Default")
      (node (ref "U1") (pin "17") (pinfunction "MOSI_17") (pintype "bidirectional"))
    )
    (net (code "121") (name "unconnected-(U1-NC-Pad14)") (class "Default")
      (node (ref "U1") (pin "14") (pinfunction "NC_14") (pintype "bidirectional"))
    )
    (net (code "122") (name "unconnected-(U1-PCM_CLK-Pad5)") (class "Default")
      (node (ref "U1") (pin "5") (pinfunction "PCM_CLK_5") (pintype "bidirectional"))
    )
    (net (code "123") (name "unconnected-(U1-PCM_IN-Pad7)") (class "Default")
      (node (ref "U1") (pin "7") (pinfunction "PCM_IN_7") (pintype "bidirectional"))
    )
    (net (code "124") (name "unconnected-(U1-PCM_OUT-Pad6)") (class "Default")
      (node (ref "U1") (pin "6") (pinfunction "PCM_OUT_6") (pintype "bidirectional"))
    )
    (net (code "125") (name "unconnected-(U1-PCN_SYNC-Pad8)") (class "Default")
      (node (ref "U1") (pin "8") (pinfunction "PCN_SYNC_8") (pintype "bidirectional"))
    )
    (net (code "126") (name "unconnected-(U1-PIO0-Pad23)") (class "Default")
      (node (ref "U1") (pin "23") (pinfunction "PIO0_23") (pintype "bidirectional"))
    )
    (net (code "127") (name "unconnected-(U1-PIO1-Pad24)") (class "Default")
      (node (ref "U1") (pin "24") (pinfunction "PIO1_24") (pintype "bidirectional"))
    )
    (net (code "128") (name "unconnected-(U1-PIO2-Pad25)") (class "Default")
      (node (ref "U1") (pin "25") (pinfunction "PIO2_25") (pintype "bidirectional"))
    )
    (net (code "129") (name "unconnected-(U1-PIO3-Pad26)") (class "Default")
      (node (ref "U1") (pin "26") (pinfunction "PIO3_26") (pintype "bidirectional"))
    )
    (net (code "130") (name "unconnected-(U1-PIO4-Pad27)") (class "Default")
      (node (ref "U1") (pin "27") (pinfunction "PIO4_27") (pintype "bidirectional"))
    )
    (net (code "131") (name "unconnected-(U1-PIO5-Pad28)") (class "Default")
      (node (ref "U1") (pin "28") (pinfunction "PIO5_28") (pintype "bidirectional"))
    )
    (net (code "132") (name "unconnected-(U1-PIO6-Pad29)") (class "Default")
      (node (ref "U1") (pin "29") (pinfunction "PIO6_29") (pintype "bidirectional"))
    )
    (net (code "133") (name "unconnected-(U1-PIO7-Pad30)") (class "Default")
      (node (ref "U1") (pin "30") (pinfunction "PIO7_30") (pintype "bidirectional"))
    )
    (net (code "134") (name "unconnected-(U1-PIO9-Pad32)") (class "Default")
      (node (ref "U1") (pin "32") (pinfunction "PIO9_32") (pintype "bidirectional"))
    )
    (net (code "135") (name "unconnected-(U1-PIO10-Pad33)") (class "Default")
      (node (ref "U1") (pin "33") (pinfunction "PIO10_33") (pintype "bidirectional"))
    )
    (net (code "136") (name "unconnected-(U1-RST-Pad11)") (class "Default")
      (node (ref "U1") (pin "11") (pinfunction "RST_11") (pintype "bidirectional"))
    )
    (net (code "137") (name "unconnected-(U1-RTS-Pad4)") (class "Default")
      (node (ref "U1") (pin "4") (pinfunction "RTS_4") (pintype "bidirectional"))
    )
    (net (code "138") (name "unconnected-(U1-VBUSD+-Pad20)") (class "Default")
      (node (ref "U1") (pin "20") (pinfunction "VBUSD+_20") (pintype "bidirectional"))
    )
    (net (code "139") (name "unconnected-(U1-VBUSD--Pad15)") (class "Default")
      (node (ref "U1") (pin "15") (pinfunction "VBUSD-_15") (pintype "bidirectional"))
    )
  )
)
